# HD68_BNC_Breakout.net
KiCad netlist of a schematic drawn in Altium Designer
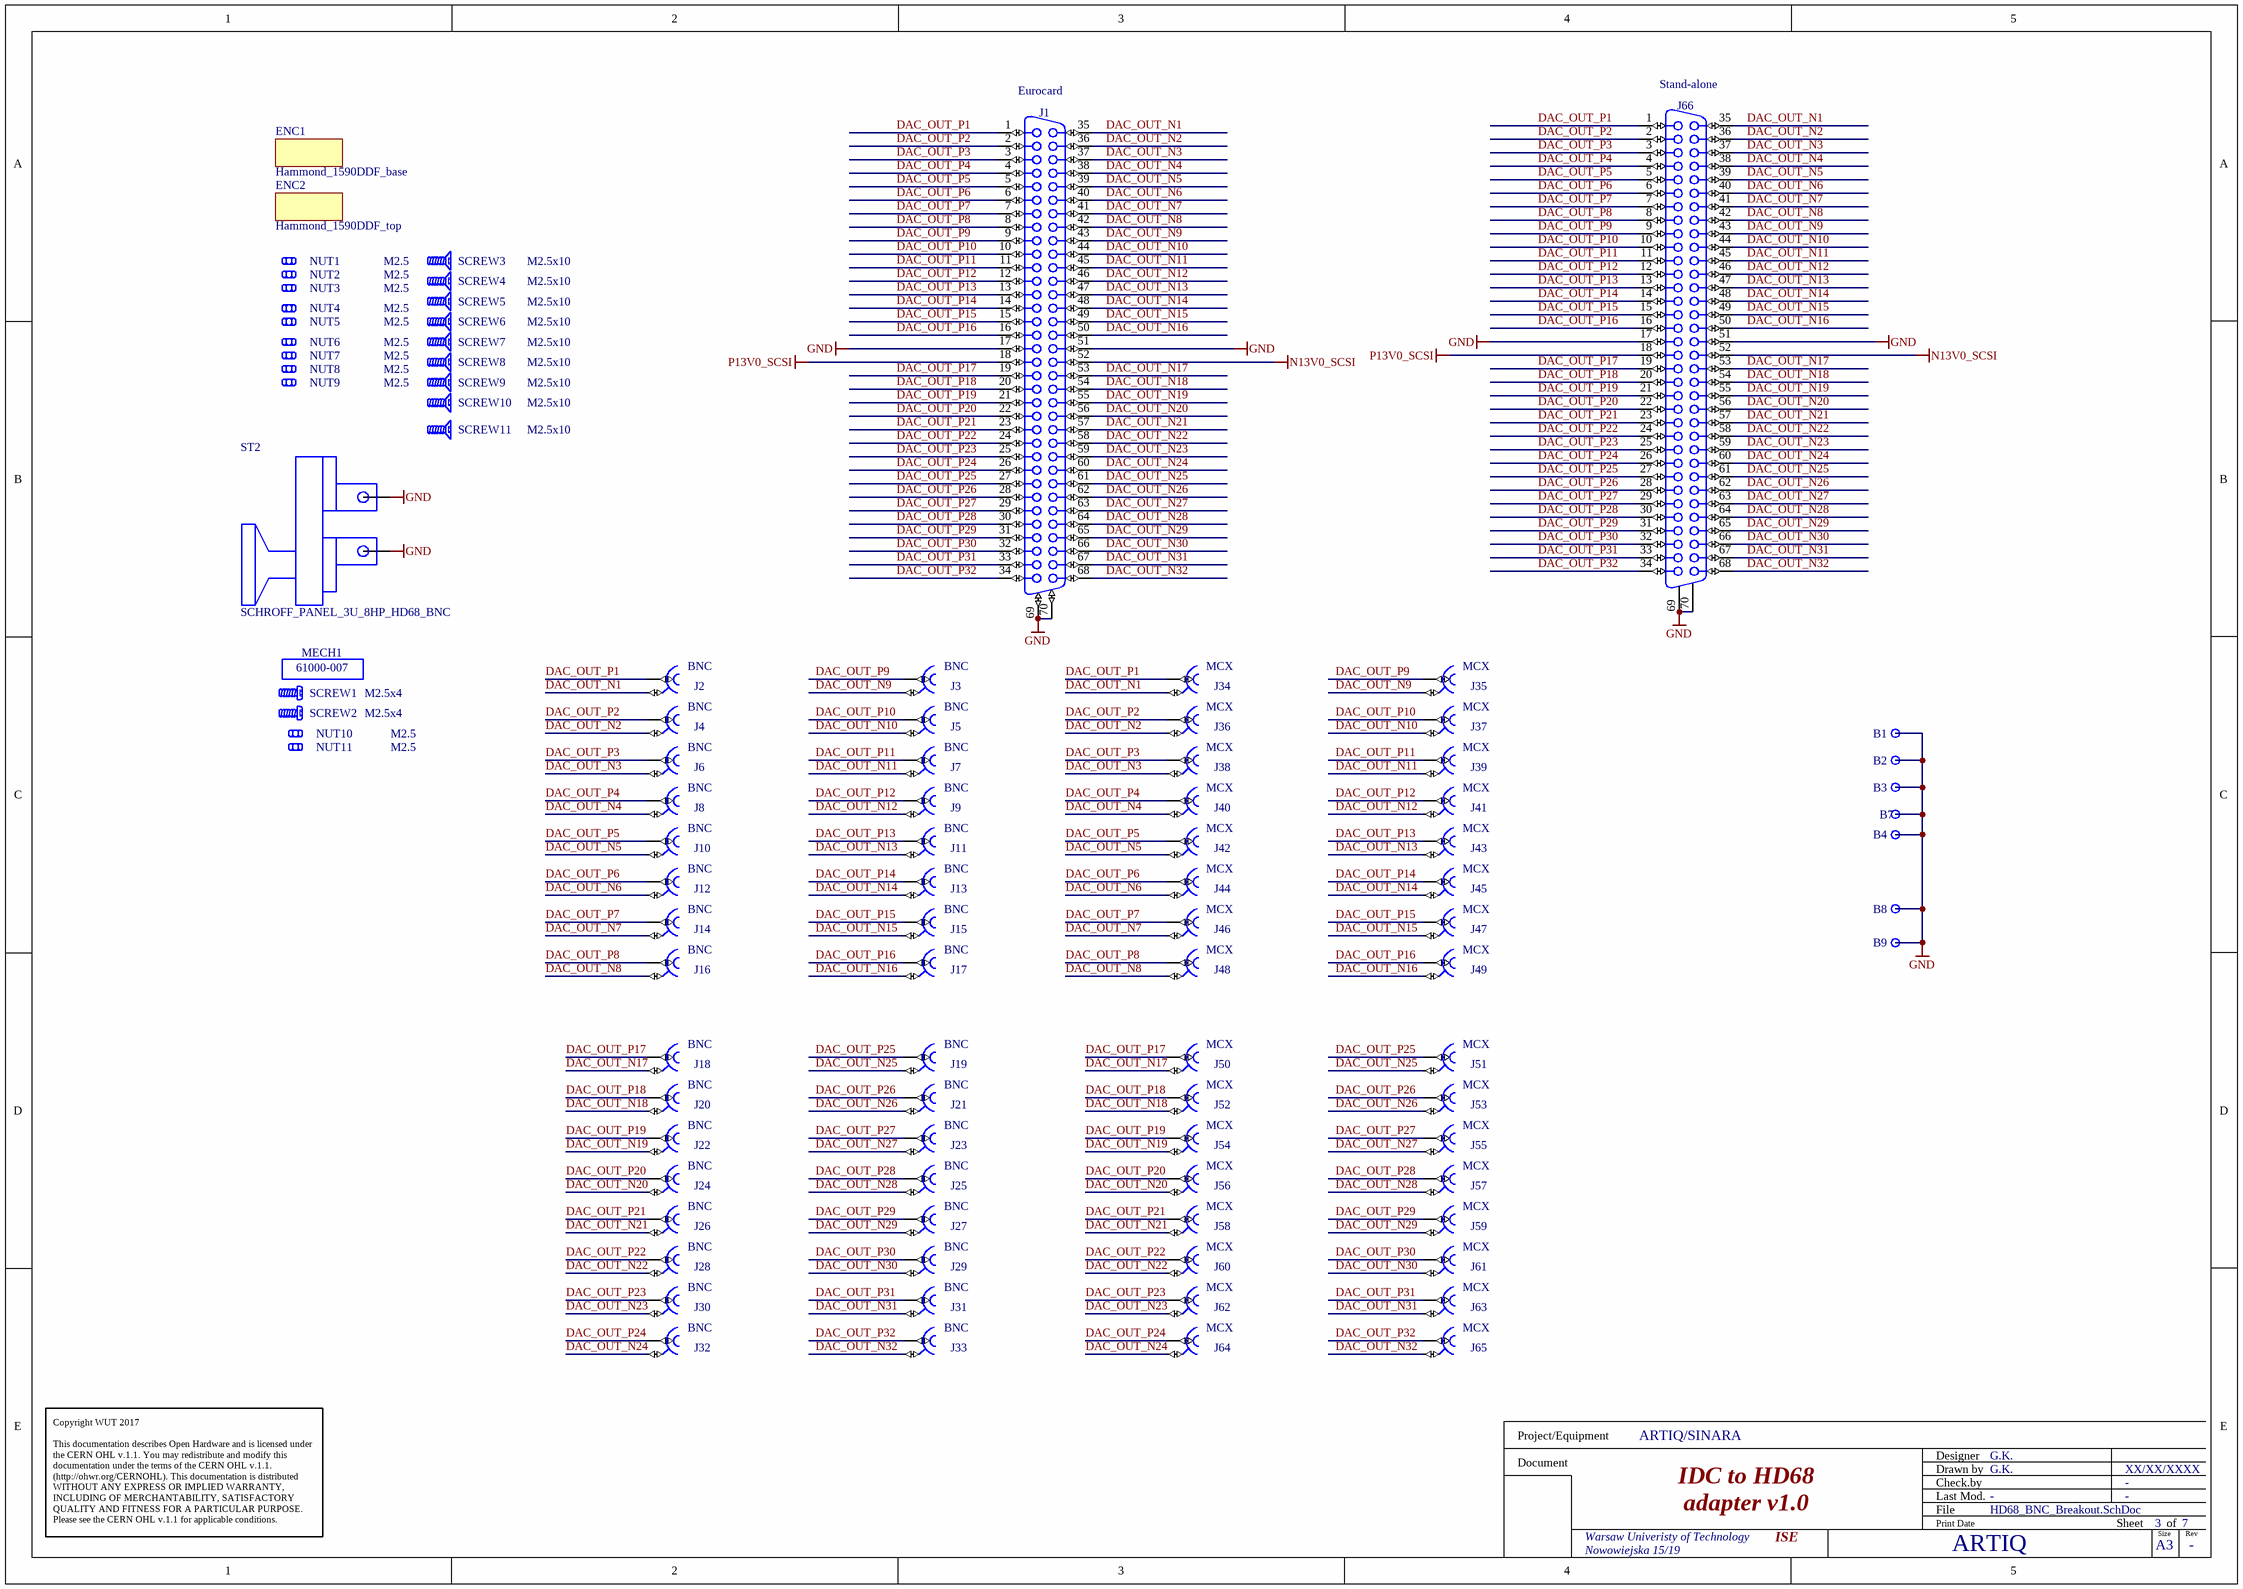
[diagram p0: HD68_BNC_Breakout.SchDoc]

(export (version "E")
  (design (tool "Eeschema 10.0.6"))
  (components
    (comp (ref "B1")
      (value "Plated Hole")
      (footprint "MTG270_500")
      (description "Single Terminal Socket")
      (fields (field (name "PART NUMBER") "PLATED_HOLE2.7_PAD5.0") (field (name "AUTHOR") "CERN DEM JMW"))
      (libsource (lib "Eletro-mechanical") (part "Single Terminal Socket"))
    )
    (comp (ref "B2")
      (value "Plated Hole")
      (footprint "MTG270_500")
      (description "Single Terminal Socket")
      (fields (field (name "PART NUMBER") "PLATED_HOLE2.7_PAD5.0") (field (name "AUTHOR") "CERN DEM JMW"))
      (libsource (lib "Eletro-mechanical") (part "Single Terminal Socket"))
    )
    (comp (ref "B3")
      (value "Plated Hole")
      (footprint "MTG270_500")
      (description "Single Terminal Socket")
      (fields (field (name "PART NUMBER") "PLATED_HOLE2.7_PAD5.0") (field (name "AUTHOR") "CERN DEM JMW"))
      (libsource (lib "Eletro-mechanical") (part "Single Terminal Socket"))
    )
    (comp (ref "B4")
      (value "Plated Hole")
      (footprint "MTG270_500")
      (description "Single Terminal Socket")
      (fields (field (name "PART NUMBER") "PLATED_HOLE2.7_PAD5.0") (field (name "AUTHOR") "CERN DEM JMW"))
      (libsource (lib "Eletro-mechanical") (part "Single Terminal Socket"))
    )
    (comp (ref "B7")
      (value "Plated Hole")
      (footprint "MTG270_500")
      (description "Single Terminal Socket")
      (fields (field (name "PART NUMBER") "PLATED_HOLE2.7_PAD5.0") (field (name "AUTHOR") "CERN DEM JMW"))
      (libsource (lib "Eletro-mechanical") (part "Single Terminal Socket"))
    )
    (comp (ref "B8")
      (value "Plated Hole")
      (footprint "MTG270_500")
      (description "Single Terminal Socket")
      (fields (field (name "PART NUMBER") "PLATED_HOLE2.7_PAD5.0") (field (name "AUTHOR") "CERN DEM JMW"))
      (libsource (lib "Eletro-mechanical") (part "Single Terminal Socket"))
    )
    (comp (ref "B9")
      (value "Plated Hole")
      (footprint "MTG270_500")
      (description "Single Terminal Socket")
      (fields (field (name "PART NUMBER") "PLATED_HOLE2.7_PAD5.0") (field (name "AUTHOR") "CERN DEM JMW"))
      (libsource (lib "Eletro-mechanical") (part "Single Terminal Socket"))
    )
    (comp (ref "ENC1")
      (value "Hammond_1590DDF_base")
      (footprint "1590DDF_base")
      (description "Hammond 1590DDF enclosure base part")
      (libsource (lib "Mechanical") (part "Hammond_1590DDF_base"))
    )
    (comp (ref "ENC2")
      (value "Hammond_1590DDF_top")
      (footprint "1590D-DD-E_LID_custom")
      (description "Hammond 1590DDF enclosure lid with custom cutouts")
      (libsource (lib "Mechanical") (part "Hammond_1590DDF_top_custom"))
    )
    (comp (ref "J1")
      (value "D-SUB")
      (footprint "TYCO_5787082-7")
      (description "68 contacts, AMPLIMITE .050\", Right Angled Receptacle Series III")
      (fields
        (field (name "PART NUMBER") "TYCO_5787082-7")
        (field (name "MANUFACTURER") "TYCO ELECTRONICS")
        (field (name "AUTHOR") "CERN DEM JLC")
      )
      (libsource (lib "Connectors") (part "TYCO_5787082-7"))
    )
    (comp (ref "J2")
      (value "BNC")
      (footprint "TYCO_5-1634506-1")
      (fields
        (field (name "PART NUMBER") "TYCO_5-1634506-1")
        (field (name "MANUFACTURER") "TYCO ELECTRONICS")
        (field (name "MANUFACTURER PART NUMBER") "5-1634506-1")
        (field (name "AUTHOR") "CERN DEM JLC")
      )
      (libsource (lib "Connectors") (part "Coax_1Female_1Shield"))
    )
    (comp (ref "J3")
      (value "BNC")
      (footprint "TYCO_5-1634506-1")
      (fields
        (field (name "PART NUMBER") "TYCO_5-1634506-1")
        (field (name "MANUFACTURER") "TYCO ELECTRONICS")
        (field (name "MANUFACTURER PART NUMBER") "5-1634506-1")
        (field (name "AUTHOR") "CERN DEM JLC")
      )
      (libsource (lib "Connectors") (part "Coax_1Female_1Shield"))
    )
    (comp (ref "J4")
      (value "BNC")
      (footprint "TYCO_5-1634506-1")
      (fields
        (field (name "PART NUMBER") "TYCO_5-1634506-1")
        (field (name "MANUFACTURER") "TYCO ELECTRONICS")
        (field (name "MANUFACTURER PART NUMBER") "5-1634506-1")
        (field (name "AUTHOR") "CERN DEM JLC")
      )
      (libsource (lib "Connectors") (part "Coax_1Female_1Shield"))
    )
    (comp (ref "J5")
      (value "BNC")
      (footprint "TYCO_5-1634506-1")
      (fields
        (field (name "PART NUMBER") "TYCO_5-1634506-1")
        (field (name "MANUFACTURER") "TYCO ELECTRONICS")
        (field (name "MANUFACTURER PART NUMBER") "5-1634506-1")
        (field (name "AUTHOR") "CERN DEM JLC")
      )
      (libsource (lib "Connectors") (part "Coax_1Female_1Shield"))
    )
    (comp (ref "J6")
      (value "BNC")
      (footprint "TYCO_5-1634506-1")
      (fields
        (field (name "PART NUMBER") "TYCO_5-1634506-1")
        (field (name "MANUFACTURER") "TYCO ELECTRONICS")
        (field (name "MANUFACTURER PART NUMBER") "5-1634506-1")
        (field (name "AUTHOR") "CERN DEM JLC")
      )
      (libsource (lib "Connectors") (part "Coax_1Female_1Shield"))
    )
    (comp (ref "J7")
      (value "BNC")
      (footprint "TYCO_5-1634506-1")
      (fields
        (field (name "PART NUMBER") "TYCO_5-1634506-1")
        (field (name "MANUFACTURER") "TYCO ELECTRONICS")
        (field (name "MANUFACTURER PART NUMBER") "5-1634506-1")
        (field (name "AUTHOR") "CERN DEM JLC")
      )
      (libsource (lib "Connectors") (part "Coax_1Female_1Shield"))
    )
    (comp (ref "J8")
      (value "BNC")
      (footprint "TYCO_5-1634506-1")
      (fields
        (field (name "PART NUMBER") "TYCO_5-1634506-1")
        (field (name "MANUFACTURER") "TYCO ELECTRONICS")
        (field (name "MANUFACTURER PART NUMBER") "5-1634506-1")
        (field (name "AUTHOR") "CERN DEM JLC")
      )
      (libsource (lib "Connectors") (part "Coax_1Female_1Shield"))
    )
    (comp (ref "J9")
      (value "BNC")
      (footprint "TYCO_5-1634506-1")
      (fields
        (field (name "PART NUMBER") "TYCO_5-1634506-1")
        (field (name "MANUFACTURER") "TYCO ELECTRONICS")
        (field (name "MANUFACTURER PART NUMBER") "5-1634506-1")
        (field (name "AUTHOR") "CERN DEM JLC")
      )
      (libsource (lib "Connectors") (part "Coax_1Female_1Shield"))
    )
    (comp (ref "J10")
      (value "BNC")
      (footprint "TYCO_5-1634506-1")
      (fields
        (field (name "PART NUMBER") "TYCO_5-1634506-1")
        (field (name "MANUFACTURER") "TYCO ELECTRONICS")
        (field (name "MANUFACTURER PART NUMBER") "5-1634506-1")
        (field (name "AUTHOR") "CERN DEM JLC")
      )
      (libsource (lib "Connectors") (part "Coax_1Female_1Shield"))
    )
    (comp (ref "J11")
      (value "BNC")
      (footprint "TYCO_5-1634506-1")
      (fields
        (field (name "PART NUMBER") "TYCO_5-1634506-1")
        (field (name "MANUFACTURER") "TYCO ELECTRONICS")
        (field (name "MANUFACTURER PART NUMBER") "5-1634506-1")
        (field (name "AUTHOR") "CERN DEM JLC")
      )
      (libsource (lib "Connectors") (part "Coax_1Female_1Shield"))
    )
    (comp (ref "J12")
      (value "BNC")
      (footprint "TYCO_5-1634506-1")
      (fields
        (field (name "PART NUMBER") "TYCO_5-1634506-1")
        (field (name "MANUFACTURER") "TYCO ELECTRONICS")
        (field (name "MANUFACTURER PART NUMBER") "5-1634506-1")
        (field (name "AUTHOR") "CERN DEM JLC")
      )
      (libsource (lib "Connectors") (part "Coax_1Female_1Shield"))
    )
    (comp (ref "J13")
      (value "BNC")
      (footprint "TYCO_5-1634506-1")
      (fields
        (field (name "PART NUMBER") "TYCO_5-1634506-1")
        (field (name "MANUFACTURER") "TYCO ELECTRONICS")
        (field (name "MANUFACTURER PART NUMBER") "5-1634506-1")
        (field (name "AUTHOR") "CERN DEM JLC")
      )
      (libsource (lib "Connectors") (part "Coax_1Female_1Shield"))
    )
    (comp (ref "J14")
      (value "BNC")
      (footprint "TYCO_5-1634506-1")
      (fields
        (field (name "PART NUMBER") "TYCO_5-1634506-1")
        (field (name "MANUFACTURER") "TYCO ELECTRONICS")
        (field (name "MANUFACTURER PART NUMBER") "5-1634506-1")
        (field (name "AUTHOR") "CERN DEM JLC")
      )
      (libsource (lib "Connectors") (part "Coax_1Female_1Shield"))
    )
    (comp (ref "J15")
      (value "BNC")
      (footprint "TYCO_5-1634506-1")
      (fields
        (field (name "PART NUMBER") "TYCO_5-1634506-1")
        (field (name "MANUFACTURER") "TYCO ELECTRONICS")
        (field (name "MANUFACTURER PART NUMBER") "5-1634506-1")
        (field (name "AUTHOR") "CERN DEM JLC")
      )
      (libsource (lib "Connectors") (part "Coax_1Female_1Shield"))
    )
    (comp (ref "J16")
      (value "BNC")
      (footprint "TYCO_5-1634506-1")
      (fields
        (field (name "PART NUMBER") "TYCO_5-1634506-1")
        (field (name "MANUFACTURER") "TYCO ELECTRONICS")
        (field (name "MANUFACTURER PART NUMBER") "5-1634506-1")
        (field (name "AUTHOR") "CERN DEM JLC")
      )
      (libsource (lib "Connectors") (part "Coax_1Female_1Shield"))
    )
    (comp (ref "J17")
      (value "BNC")
      (footprint "TYCO_5-1634506-1")
      (fields
        (field (name "PART NUMBER") "TYCO_5-1634506-1")
        (field (name "MANUFACTURER") "TYCO ELECTRONICS")
        (field (name "MANUFACTURER PART NUMBER") "5-1634506-1")
        (field (name "AUTHOR") "CERN DEM JLC")
      )
      (libsource (lib "Connectors") (part "Coax_1Female_1Shield"))
    )
    (comp (ref "J18")
      (value "BNC")
      (footprint "TYCO_5-1634506-1")
      (fields
        (field (name "PART NUMBER") "TYCO_5-1634506-1")
        (field (name "MANUFACTURER") "TYCO ELECTRONICS")
        (field (name "MANUFACTURER PART NUMBER") "5-1634506-1")
        (field (name "AUTHOR") "CERN DEM JLC")
      )
      (libsource (lib "Connectors") (part "Coax_1Female_1Shield"))
    )
    (comp (ref "J19")
      (value "BNC")
      (footprint "TYCO_5-1634506-1")
      (fields
        (field (name "PART NUMBER") "TYCO_5-1634506-1")
        (field (name "MANUFACTURER") "TYCO ELECTRONICS")
        (field (name "MANUFACTURER PART NUMBER") "5-1634506-1")
        (field (name "AUTHOR") "CERN DEM JLC")
      )
      (libsource (lib "Connectors") (part "Coax_1Female_1Shield"))
    )
    (comp (ref "J20")
      (value "BNC")
      (footprint "TYCO_5-1634506-1")
      (fields
        (field (name "PART NUMBER") "TYCO_5-1634506-1")
        (field (name "MANUFACTURER") "TYCO ELECTRONICS")
        (field (name "MANUFACTURER PART NUMBER") "5-1634506-1")
        (field (name "AUTHOR") "CERN DEM JLC")
      )
      (libsource (lib "Connectors") (part "Coax_1Female_1Shield"))
    )
    (comp (ref "J21")
      (value "BNC")
      (footprint "TYCO_5-1634506-1")
      (fields
        (field (name "PART NUMBER") "TYCO_5-1634506-1")
        (field (name "MANUFACTURER") "TYCO ELECTRONICS")
        (field (name "MANUFACTURER PART NUMBER") "5-1634506-1")
        (field (name "AUTHOR") "CERN DEM JLC")
      )
      (libsource (lib "Connectors") (part "Coax_1Female_1Shield"))
    )
    (comp (ref "J22")
      (value "BNC")
      (footprint "TYCO_5-1634506-1")
      (fields
        (field (name "PART NUMBER") "TYCO_5-1634506-1")
        (field (name "MANUFACTURER") "TYCO ELECTRONICS")
        (field (name "MANUFACTURER PART NUMBER") "5-1634506-1")
        (field (name "AUTHOR") "CERN DEM JLC")
      )
      (libsource (lib "Connectors") (part "Coax_1Female_1Shield"))
    )
    (comp (ref "J23")
      (value "BNC")
      (footprint "TYCO_5-1634506-1")
      (fields
        (field (name "PART NUMBER") "TYCO_5-1634506-1")
        (field (name "MANUFACTURER") "TYCO ELECTRONICS")
        (field (name "MANUFACTURER PART NUMBER") "5-1634506-1")
        (field (name "AUTHOR") "CERN DEM JLC")
      )
      (libsource (lib "Connectors") (part "Coax_1Female_1Shield"))
    )
    (comp (ref "J24")
      (value "BNC")
      (footprint "TYCO_5-1634506-1")
      (fields
        (field (name "PART NUMBER") "TYCO_5-1634506-1")
        (field (name "MANUFACTURER") "TYCO ELECTRONICS")
        (field (name "MANUFACTURER PART NUMBER") "5-1634506-1")
        (field (name "AUTHOR") "CERN DEM JLC")
      )
      (libsource (lib "Connectors") (part "Coax_1Female_1Shield"))
    )
    (comp (ref "J25")
      (value "BNC")
      (footprint "TYCO_5-1634506-1")
      (fields
        (field (name "PART NUMBER") "TYCO_5-1634506-1")
        (field (name "MANUFACTURER") "TYCO ELECTRONICS")
        (field (name "MANUFACTURER PART NUMBER") "5-1634506-1")
        (field (name "AUTHOR") "CERN DEM JLC")
      )
      (libsource (lib "Connectors") (part "Coax_1Female_1Shield"))
    )
    (comp (ref "J26")
      (value "BNC")
      (footprint "TYCO_5-1634506-1")
      (fields
        (field (name "PART NUMBER") "TYCO_5-1634506-1")
        (field (name "MANUFACTURER") "TYCO ELECTRONICS")
        (field (name "MANUFACTURER PART NUMBER") "5-1634506-1")
        (field (name "AUTHOR") "CERN DEM JLC")
      )
      (libsource (lib "Connectors") (part "Coax_1Female_1Shield"))
    )
    (comp (ref "J27")
      (value "BNC")
      (footprint "TYCO_5-1634506-1")
      (fields
        (field (name "PART NUMBER") "TYCO_5-1634506-1")
        (field (name "MANUFACTURER") "TYCO ELECTRONICS")
        (field (name "MANUFACTURER PART NUMBER") "5-1634506-1")
        (field (name "AUTHOR") "CERN DEM JLC")
      )
      (libsource (lib "Connectors") (part "Coax_1Female_1Shield"))
    )
    (comp (ref "J28")
      (value "BNC")
      (footprint "TYCO_5-1634506-1")
      (fields
        (field (name "PART NUMBER") "TYCO_5-1634506-1")
        (field (name "MANUFACTURER") "TYCO ELECTRONICS")
        (field (name "MANUFACTURER PART NUMBER") "5-1634506-1")
        (field (name "AUTHOR") "CERN DEM JLC")
      )
      (libsource (lib "Connectors") (part "Coax_1Female_1Shield"))
    )
    (comp (ref "J29")
      (value "BNC")
      (footprint "TYCO_5-1634506-1")
      (fields
        (field (name "PART NUMBER") "TYCO_5-1634506-1")
        (field (name "MANUFACTURER") "TYCO ELECTRONICS")
        (field (name "MANUFACTURER PART NUMBER") "5-1634506-1")
        (field (name "AUTHOR") "CERN DEM JLC")
      )
      (libsource (lib "Connectors") (part "Coax_1Female_1Shield"))
    )
    (comp (ref "J30")
      (value "BNC")
      (footprint "TYCO_5-1634506-1")
      (fields
        (field (name "PART NUMBER") "TYCO_5-1634506-1")
        (field (name "MANUFACTURER") "TYCO ELECTRONICS")
        (field (name "MANUFACTURER PART NUMBER") "5-1634506-1")
        (field (name "AUTHOR") "CERN DEM JLC")
      )
      (libsource (lib "Connectors") (part "Coax_1Female_1Shield"))
    )
    (comp (ref "J31")
      (value "BNC")
      (footprint "TYCO_5-1634506-1")
      (fields
        (field (name "PART NUMBER") "TYCO_5-1634506-1")
        (field (name "MANUFACTURER") "TYCO ELECTRONICS")
        (field (name "MANUFACTURER PART NUMBER") "5-1634506-1")
        (field (name "AUTHOR") "CERN DEM JLC")
      )
      (libsource (lib "Connectors") (part "Coax_1Female_1Shield"))
    )
    (comp (ref "J32")
      (value "BNC")
      (footprint "TYCO_5-1634506-1")
      (fields
        (field (name "PART NUMBER") "TYCO_5-1634506-1")
        (field (name "MANUFACTURER") "TYCO ELECTRONICS")
        (field (name "MANUFACTURER PART NUMBER") "5-1634506-1")
        (field (name "AUTHOR") "CERN DEM JLC")
      )
      (libsource (lib "Connectors") (part "Coax_1Female_1Shield"))
    )
    (comp (ref "J33")
      (value "BNC")
      (footprint "TYCO_5-1634506-1")
      (fields
        (field (name "PART NUMBER") "TYCO_5-1634506-1")
        (field (name "MANUFACTURER") "TYCO ELECTRONICS")
        (field (name "MANUFACTURER PART NUMBER") "5-1634506-1")
        (field (name "AUTHOR") "CERN DEM JLC")
      )
      (libsource (lib "Connectors") (part "Coax_1Female_1Shield"))
    )
    (comp (ref "J34")
      (value "MCX")
      (footprint "AMPHENOL_919-109J-51PX")
      (fields
        (field (name "PART NUMBER") "AMPHENOL_919-109J-51PX")
        (field (name "MANUFACTURER") "AMPHENOL")
        (field (name "MANUFACTURER PART NUMBER") "919-109J-51PX (MCX6251B1-3GT30G-50)")
        (field (name "AUTHOR") "CERN DEM BC")
      )
      (libsource (lib "Connectors") (part "Coax_1Female_1Shield"))
    )
    (comp (ref "J35")
      (value "MCX")
      (footprint "AMPHENOL_919-109J-51PX")
      (fields
        (field (name "PART NUMBER") "AMPHENOL_919-109J-51PX")
        (field (name "MANUFACTURER") "AMPHENOL")
        (field (name "MANUFACTURER PART NUMBER") "919-109J-51PX (MCX6251B1-3GT30G-50)")
        (field (name "AUTHOR") "CERN DEM BC")
      )
      (libsource (lib "Connectors") (part "Coax_1Female_1Shield"))
    )
    (comp (ref "J36")
      (value "MCX")
      (footprint "AMPHENOL_919-109J-51PX")
      (fields
        (field (name "PART NUMBER") "AMPHENOL_919-109J-51PX")
        (field (name "MANUFACTURER") "AMPHENOL")
        (field (name "MANUFACTURER PART NUMBER") "919-109J-51PX (MCX6251B1-3GT30G-50)")
        (field (name "AUTHOR") "CERN DEM BC")
      )
      (libsource (lib "Connectors") (part "Coax_1Female_1Shield"))
    )
    (comp (ref "J37")
      (value "MCX")
      (footprint "AMPHENOL_919-109J-51PX")
      (fields
        (field (name "PART NUMBER") "AMPHENOL_919-109J-51PX")
        (field (name "MANUFACTURER") "AMPHENOL")
        (field (name "MANUFACTURER PART NUMBER") "919-109J-51PX (MCX6251B1-3GT30G-50)")
        (field (name "AUTHOR") "CERN DEM BC")
      )
      (libsource (lib "Connectors") (part "Coax_1Female_1Shield"))
    )
    (comp (ref "J38")
      (value "MCX")
      (footprint "AMPHENOL_919-109J-51PX")
      (fields
        (field (name "PART NUMBER") "AMPHENOL_919-109J-51PX")
        (field (name "MANUFACTURER") "AMPHENOL")
        (field (name "MANUFACTURER PART NUMBER") "919-109J-51PX (MCX6251B1-3GT30G-50)")
        (field (name "AUTHOR") "CERN DEM BC")
      )
      (libsource (lib "Connectors") (part "Coax_1Female_1Shield"))
    )
    (comp (ref "J39")
      (value "MCX")
      (footprint "AMPHENOL_919-109J-51PX")
      (fields
        (field (name "PART NUMBER") "AMPHENOL_919-109J-51PX")
        (field (name "MANUFACTURER") "AMPHENOL")
        (field (name "MANUFACTURER PART NUMBER") "919-109J-51PX (MCX6251B1-3GT30G-50)")
        (field (name "AUTHOR") "CERN DEM BC")
      )
      (libsource (lib "Connectors") (part "Coax_1Female_1Shield"))
    )
    (comp (ref "J40")
      (value "MCX")
      (footprint "AMPHENOL_919-109J-51PX")
      (fields
        (field (name "PART NUMBER") "AMPHENOL_919-109J-51PX")
        (field (name "MANUFACTURER") "AMPHENOL")
        (field (name "MANUFACTURER PART NUMBER") "919-109J-51PX (MCX6251B1-3GT30G-50)")
        (field (name "AUTHOR") "CERN DEM BC")
      )
      (libsource (lib "Connectors") (part "Coax_1Female_1Shield"))
    )
    (comp (ref "J41")
      (value "MCX")
      (footprint "AMPHENOL_919-109J-51PX")
      (fields
        (field (name "PART NUMBER") "AMPHENOL_919-109J-51PX")
        (field (name "MANUFACTURER") "AMPHENOL")
        (field (name "MANUFACTURER PART NUMBER") "919-109J-51PX (MCX6251B1-3GT30G-50)")
        (field (name "AUTHOR") "CERN DEM BC")
      )
      (libsource (lib "Connectors") (part "Coax_1Female_1Shield"))
    )
    (comp (ref "J42")
      (value "MCX")
      (footprint "AMPHENOL_919-109J-51PX")
      (fields
        (field (name "PART NUMBER") "AMPHENOL_919-109J-51PX")
        (field (name "MANUFACTURER") "AMPHENOL")
        (field (name "MANUFACTURER PART NUMBER") "919-109J-51PX (MCX6251B1-3GT30G-50)")
        (field (name "AUTHOR") "CERN DEM BC")
      )
      (libsource (lib "Connectors") (part "Coax_1Female_1Shield"))
    )
    (comp (ref "J43")
      (value "MCX")
      (footprint "AMPHENOL_919-109J-51PX")
      (fields
        (field (name "PART NUMBER") "AMPHENOL_919-109J-51PX")
        (field (name "MANUFACTURER") "AMPHENOL")
        (field (name "MANUFACTURER PART NUMBER") "919-109J-51PX (MCX6251B1-3GT30G-50)")
        (field (name "AUTHOR") "CERN DEM BC")
      )
      (libsource (lib "Connectors") (part "Coax_1Female_1Shield"))
    )
    (comp (ref "J44")
      (value "MCX")
      (footprint "AMPHENOL_919-109J-51PX")
      (fields
        (field (name "PART NUMBER") "AMPHENOL_919-109J-51PX")
        (field (name "MANUFACTURER") "AMPHENOL")
        (field (name "MANUFACTURER PART NUMBER") "919-109J-51PX (MCX6251B1-3GT30G-50)")
        (field (name "AUTHOR") "CERN DEM BC")
      )
      (libsource (lib "Connectors") (part "Coax_1Female_1Shield"))
    )
    (comp (ref "J45")
      (value "MCX")
      (footprint "AMPHENOL_919-109J-51PX")
      (fields
        (field (name "PART NUMBER") "AMPHENOL_919-109J-51PX")
        (field (name "MANUFACTURER") "AMPHENOL")
        (field (name "MANUFACTURER PART NUMBER") "919-109J-51PX (MCX6251B1-3GT30G-50)")
        (field (name "AUTHOR") "CERN DEM BC")
      )
      (libsource (lib "Connectors") (part "Coax_1Female_1Shield"))
    )
    (comp (ref "J46")
      (value "MCX")
      (footprint "AMPHENOL_919-109J-51PX")
      (fields
        (field (name "PART NUMBER") "AMPHENOL_919-109J-51PX")
        (field (name "MANUFACTURER") "AMPHENOL")
        (field (name "MANUFACTURER PART NUMBER") "919-109J-51PX (MCX6251B1-3GT30G-50)")
        (field (name "AUTHOR") "CERN DEM BC")
      )
      (libsource (lib "Connectors") (part "Coax_1Female_1Shield"))
    )
    (comp (ref "J47")
      (value "MCX")
      (footprint "AMPHENOL_919-109J-51PX")
      (fields
        (field (name "PART NUMBER") "AMPHENOL_919-109J-51PX")
        (field (name "MANUFACTURER") "AMPHENOL")
        (field (name "MANUFACTURER PART NUMBER") "919-109J-51PX (MCX6251B1-3GT30G-50)")
        (field (name "AUTHOR") "CERN DEM BC")
      )
      (libsource (lib "Connectors") (part "Coax_1Female_1Shield"))
    )
    (comp (ref "J48")
      (value "MCX")
      (footprint "AMPHENOL_919-109J-51PX")
      (fields
        (field (name "PART NUMBER") "AMPHENOL_919-109J-51PX")
        (field (name "MANUFACTURER") "AMPHENOL")
        (field (name "MANUFACTURER PART NUMBER") "919-109J-51PX (MCX6251B1-3GT30G-50)")
        (field (name "AUTHOR") "CERN DEM BC")
      )
      (libsource (lib "Connectors") (part "Coax_1Female_1Shield"))
    )
    (comp (ref "J49")
      (value "MCX")
      (footprint "AMPHENOL_919-109J-51PX")
      (fields
        (field (name "PART NUMBER") "AMPHENOL_919-109J-51PX")
        (field (name "MANUFACTURER") "AMPHENOL")
        (field (name "MANUFACTURER PART NUMBER") "919-109J-51PX (MCX6251B1-3GT30G-50)")
        (field (name "AUTHOR") "CERN DEM BC")
      )
      (libsource (lib "Connectors") (part "Coax_1Female_1Shield"))
    )
    (comp (ref "J50")
      (value "MCX")
      (footprint "AMPHENOL_919-109J-51PX")
      (fields
        (field (name "PART NUMBER") "AMPHENOL_919-109J-51PX")
        (field (name "MANUFACTURER") "AMPHENOL")
        (field (name "MANUFACTURER PART NUMBER") "919-109J-51PX (MCX6251B1-3GT30G-50)")
        (field (name "AUTHOR") "CERN DEM BC")
      )
      (libsource (lib "Connectors") (part "Coax_1Female_1Shield"))
    )
    (comp (ref "J51")
      (value "MCX")
      (footprint "AMPHENOL_919-109J-51PX")
      (fields
        (field (name "PART NUMBER") "AMPHENOL_919-109J-51PX")
        (field (name "MANUFACTURER") "AMPHENOL")
        (field (name "MANUFACTURER PART NUMBER") "919-109J-51PX (MCX6251B1-3GT30G-50)")
        (field (name "AUTHOR") "CERN DEM BC")
      )
      (libsource (lib "Connectors") (part "Coax_1Female_1Shield"))
    )
    (comp (ref "J52")
      (value "MCX")
      (footprint "AMPHENOL_919-109J-51PX")
      (fields
        (field (name "PART NUMBER") "AMPHENOL_919-109J-51PX")
        (field (name "MANUFACTURER") "AMPHENOL")
        (field (name "MANUFACTURER PART NUMBER") "919-109J-51PX (MCX6251B1-3GT30G-50)")
        (field (name "AUTHOR") "CERN DEM BC")
      )
      (libsource (lib "Connectors") (part "Coax_1Female_1Shield"))
    )
    (comp (ref "J53")
      (value "MCX")
      (footprint "AMPHENOL_919-109J-51PX")
      (fields
        (field (name "PART NUMBER") "AMPHENOL_919-109J-51PX")
        (field (name "MANUFACTURER") "AMPHENOL")
        (field (name "MANUFACTURER PART NUMBER") "919-109J-51PX (MCX6251B1-3GT30G-50)")
        (field (name "AUTHOR") "CERN DEM BC")
      )
      (libsource (lib "Connectors") (part "Coax_1Female_1Shield"))
    )
    (comp (ref "J54")
      (value "MCX")
      (footprint "AMPHENOL_919-109J-51PX")
      (fields
        (field (name "PART NUMBER") "AMPHENOL_919-109J-51PX")
        (field (name "MANUFACTURER") "AMPHENOL")
        (field (name "MANUFACTURER PART NUMBER") "919-109J-51PX (MCX6251B1-3GT30G-50)")
        (field (name "AUTHOR") "CERN DEM BC")
      )
      (libsource (lib "Connectors") (part "Coax_1Female_1Shield"))
    )
    (comp (ref "J55")
      (value "MCX")
      (footprint "AMPHENOL_919-109J-51PX")
      (fields
        (field (name "PART NUMBER") "AMPHENOL_919-109J-51PX")
        (field (name "MANUFACTURER") "AMPHENOL")
        (field (name "MANUFACTURER PART NUMBER") "919-109J-51PX (MCX6251B1-3GT30G-50)")
        (field (name "AUTHOR") "CERN DEM BC")
      )
      (libsource (lib "Connectors") (part "Coax_1Female_1Shield"))
    )
    (comp (ref "J56")
      (value "MCX")
      (footprint "AMPHENOL_919-109J-51PX")
      (fields
        (field (name "PART NUMBER") "AMPHENOL_919-109J-51PX")
        (field (name "MANUFACTURER") "AMPHENOL")
        (field (name "MANUFACTURER PART NUMBER") "919-109J-51PX (MCX6251B1-3GT30G-50)")
        (field (name "AUTHOR") "CERN DEM BC")
      )
      (libsource (lib "Connectors") (part "Coax_1Female_1Shield"))
    )
    (comp (ref "J57")
      (value "MCX")
      (footprint "AMPHENOL_919-109J-51PX")
      (fields
        (field (name "PART NUMBER") "AMPHENOL_919-109J-51PX")
        (field (name "MANUFACTURER") "AMPHENOL")
        (field (name "MANUFACTURER PART NUMBER") "919-109J-51PX (MCX6251B1-3GT30G-50)")
        (field (name "AUTHOR") "CERN DEM BC")
      )
      (libsource (lib "Connectors") (part "Coax_1Female_1Shield"))
    )
    (comp (ref "J58")
      (value "MCX")
      (footprint "AMPHENOL_919-109J-51PX")
      (fields
        (field (name "PART NUMBER") "AMPHENOL_919-109J-51PX")
        (field (name "MANUFACTURER") "AMPHENOL")
        (field (name "MANUFACTURER PART NUMBER") "919-109J-51PX (MCX6251B1-3GT30G-50)")
        (field (name "AUTHOR") "CERN DEM BC")
      )
      (libsource (lib "Connectors") (part "Coax_1Female_1Shield"))
    )
    (comp (ref "J59")
      (value "MCX")
      (footprint "AMPHENOL_919-109J-51PX")
      (fields
        (field (name "PART NUMBER") "AMPHENOL_919-109J-51PX")
        (field (name "MANUFACTURER") "AMPHENOL")
        (field (name "MANUFACTURER PART NUMBER") "919-109J-51PX (MCX6251B1-3GT30G-50)")
        (field (name "AUTHOR") "CERN DEM BC")
      )
      (libsource (lib "Connectors") (part "Coax_1Female_1Shield"))
    )
    (comp (ref "J60")
      (value "MCX")
      (footprint "AMPHENOL_919-109J-51PX")
      (fields
        (field (name "PART NUMBER") "AMPHENOL_919-109J-51PX")
        (field (name "MANUFACTURER") "AMPHENOL")
        (field (name "MANUFACTURER PART NUMBER") "919-109J-51PX (MCX6251B1-3GT30G-50)")
        (field (name "AUTHOR") "CERN DEM BC")
      )
      (libsource (lib "Connectors") (part "Coax_1Female_1Shield"))
    )
    (comp (ref "J61")
      (value "MCX")
      (footprint "AMPHENOL_919-109J-51PX")
      (fields
        (field (name "PART NUMBER") "AMPHENOL_919-109J-51PX")
        (field (name "MANUFACTURER") "AMPHENOL")
        (field (name "MANUFACTURER PART NUMBER") "919-109J-51PX (MCX6251B1-3GT30G-50)")
        (field (name "AUTHOR") "CERN DEM BC")
      )
      (libsource (lib "Connectors") (part "Coax_1Female_1Shield"))
    )
    (comp (ref "J62")
      (value "MCX")
      (footprint "AMPHENOL_919-109J-51PX")
      (fields
        (field (name "PART NUMBER") "AMPHENOL_919-109J-51PX")
        (field (name "MANUFACTURER") "AMPHENOL")
        (field (name "MANUFACTURER PART NUMBER") "919-109J-51PX (MCX6251B1-3GT30G-50)")
        (field (name "AUTHOR") "CERN DEM BC")
      )
      (libsource (lib "Connectors") (part "Coax_1Female_1Shield"))
    )
    (comp (ref "J63")
      (value "MCX")
      (footprint "AMPHENOL_919-109J-51PX")
      (fields
        (field (name "PART NUMBER") "AMPHENOL_919-109J-51PX")
        (field (name "MANUFACTURER") "AMPHENOL")
        (field (name "MANUFACTURER PART NUMBER") "919-109J-51PX (MCX6251B1-3GT30G-50)")
        (field (name "AUTHOR") "CERN DEM BC")
      )
      (libsource (lib "Connectors") (part "Coax_1Female_1Shield"))
    )
    (comp (ref "J64")
      (value "MCX")
      (footprint "AMPHENOL_919-109J-51PX")
      (fields
        (field (name "PART NUMBER") "AMPHENOL_919-109J-51PX")
        (field (name "MANUFACTURER") "AMPHENOL")
        (field (name "MANUFACTURER PART NUMBER") "919-109J-51PX (MCX6251B1-3GT30G-50)")
        (field (name "AUTHOR") "CERN DEM BC")
      )
      (libsource (lib "Connectors") (part "Coax_1Female_1Shield"))
    )
    (comp (ref "J65")
      (value "MCX")
      (footprint "AMPHENOL_919-109J-51PX")
      (fields
        (field (name "PART NUMBER") "AMPHENOL_919-109J-51PX")
        (field (name "MANUFACTURER") "AMPHENOL")
        (field (name "MANUFACTURER PART NUMBER") "919-109J-51PX (MCX6251B1-3GT30G-50)")
        (field (name "AUTHOR") "CERN DEM BC")
      )
      (libsource (lib "Connectors") (part "Coax_1Female_1Shield"))
    )
    (comp (ref "J66")
      (value "AMPLIMITE")
      (footprint "TYCO_5749721-7")
      (description "AMPLIMITE .050 Series, 68 Positions Vertical Receptacle")
      (fields
        (field (name "PART NUMBER") "TYCO_5749721-7")
        (field (name "MANUFACTURER") "TYCO ELECTRONICS")
        (field (name "AUTHOR") "CERN DEM HF")
      )
      (libsource (lib "Connectors") (part "TYCO_5749721-7"))
    )
    (comp (ref "MECH1")
      (value "61000-007")
      (footprint "GENERIC_MECH")
      (description "PCB Solder Side Cover, 3 U, 100 mm x 160 mm, 55°C Schroff insulating plate")
      (fields (field (name "MANUFACTURER") "Schroff") (field (name "AUTHOR") "GK"))
      (libsource (lib "Mechanical") (part "Generic_mechanical"))
    )
    (comp (ref "NUT1")
      (value "M2.5")
      (footprint "BOSSARD_BN628-1241427_v")
      (description "Nut")
      (fields
        (field (name "PART NUMBER") "BOSSARD_BN628-1241427_v")
        (field (name "MANUFACTURER") "BOSSARD")
        (field (name "AUTHOR") "CERN DEM JMW")
      )
      (libsource (lib "Eletro-mechanical") (part "Nut"))
    )
    (comp (ref "NUT2")
      (value "M2.5")
      (footprint "BOSSARD_BN628-1241427_v")
      (description "Nut")
      (fields
        (field (name "PART NUMBER") "BOSSARD_BN628-1241427_v")
        (field (name "MANUFACTURER") "BOSSARD")
        (field (name "AUTHOR") "CERN DEM JMW")
      )
      (libsource (lib "Eletro-mechanical") (part "Nut"))
    )
    (comp (ref "NUT3")
      (value "M2.5")
      (footprint "BOSSARD_BN628-1241427_v")
      (description "Nut")
      (fields
        (field (name "PART NUMBER") "BOSSARD_BN628-1241427_v")
        (field (name "MANUFACTURER") "BOSSARD")
        (field (name "AUTHOR") "CERN DEM JMW")
      )
      (libsource (lib "Eletro-mechanical") (part "Nut"))
    )
    (comp (ref "NUT4")
      (value "M2.5")
      (footprint "BOSSARD_BN628-1241427_v")
      (description "Nut")
      (fields
        (field (name "PART NUMBER") "BOSSARD_BN628-1241427_v")
        (field (name "MANUFACTURER") "BOSSARD")
        (field (name "AUTHOR") "CERN DEM JMW")
      )
      (libsource (lib "Eletro-mechanical") (part "Nut"))
    )
    (comp (ref "NUT5")
      (value "M2.5")
      (footprint "BOSSARD_BN628-1241427_v")
      (description "Nut")
      (fields
        (field (name "PART NUMBER") "BOSSARD_BN628-1241427_v")
        (field (name "MANUFACTURER") "BOSSARD")
        (field (name "AUTHOR") "CERN DEM JMW")
      )
      (libsource (lib "Eletro-mechanical") (part "Nut"))
    )
    (comp (ref "NUT6")
      (value "M2.5")
      (footprint "BOSSARD_BN628-1241427_v")
      (description "Nut")
      (fields
        (field (name "PART NUMBER") "BOSSARD_BN628-1241427_v")
        (field (name "MANUFACTURER") "BOSSARD")
        (field (name "AUTHOR") "CERN DEM JMW")
      )
      (libsource (lib "Eletro-mechanical") (part "Nut"))
    )
    (comp (ref "NUT7")
      (value "M2.5")
      (footprint "BOSSARD_BN628-1241427_v")
      (description "Nut")
      (fields
        (field (name "PART NUMBER") "BOSSARD_BN628-1241427_v")
        (field (name "MANUFACTURER") "BOSSARD")
        (field (name "AUTHOR") "CERN DEM JMW")
      )
      (libsource (lib "Eletro-mechanical") (part "Nut"))
    )
    (comp (ref "NUT8")
      (value "M2.5")
      (footprint "BOSSARD_BN628-1241427_v")
      (description "Nut")
      (fields
        (field (name "PART NUMBER") "BOSSARD_BN628-1241427_v")
        (field (name "MANUFACTURER") "BOSSARD")
        (field (name "AUTHOR") "CERN DEM JMW")
      )
      (libsource (lib "Eletro-mechanical") (part "Nut"))
    )
    (comp (ref "NUT9")
      (value "M2.5")
      (footprint "BOSSARD_BN628-1241427_v")
      (description "Nut")
      (fields
        (field (name "PART NUMBER") "BOSSARD_BN628-1241427_v")
        (field (name "MANUFACTURER") "BOSSARD")
        (field (name "AUTHOR") "CERN DEM JMW")
      )
      (libsource (lib "Eletro-mechanical") (part "Nut"))
    )
    (comp (ref "NUT10")
      (value "M2.5")
      (footprint "BOSSARD_BN628-1241427_v")
      (description "Nut")
      (fields
        (field (name "PART NUMBER") "BOSSARD_BN628-1241427_v")
        (field (name "MANUFACTURER") "BOSSARD")
        (field (name "AUTHOR") "CERN DEM JMW")
      )
      (libsource (lib "Eletro-mechanical") (part "Nut"))
    )
    (comp (ref "NUT11")
      (value "M2.5")
      (footprint "BOSSARD_BN628-1241427_v")
      (description "Nut")
      (fields
        (field (name "PART NUMBER") "BOSSARD_BN628-1241427_v")
        (field (name "MANUFACTURER") "BOSSARD")
        (field (name "AUTHOR") "CERN DEM JMW")
      )
      (libsource (lib "Eletro-mechanical") (part "Nut"))
    )
    (comp (ref "SCREW1")
      (value "M2.5x4")
      (footprint "BOSSARD_BN5687-3061587_v")
      (description "Screw")
      (fields
        (field (name "PART NUMBER") "BOSSARD_BN5687-3061587_v")
        (field (name "MANUFACTURER") "BOSSARD")
        (field (name "AUTHOR") "CERN DEM JLC")
      )
      (libsource (lib "Eletro-mechanical") (part "Screw"))
    )
    (comp (ref "SCREW2")
      (value "M2.5x4")
      (footprint "BOSSARD_BN5687-3061587_v")
      (description "Screw")
      (fields
        (field (name "PART NUMBER") "BOSSARD_BN5687-3061587_v")
        (field (name "MANUFACTURER") "BOSSARD")
        (field (name "AUTHOR") "CERN DEM JLC")
      )
      (libsource (lib "Eletro-mechanical") (part "Screw"))
    )
    (comp (ref "SCREW3")
      (value "M2.5x10")
      (footprint "BOSSARD_B2.5X10/BN3333_v")
      (description "Screw; 2.5x10; Head: countersunk; Philips; A1 steel")
      (fields
        (field (name "PART NUMBER") "BOSSARD_B2.5X10/BN3333")
        (field (name "MANUFACTURER") "BOSSARD")
        (field (name "AUTHOR") "GK")
      )
      (libsource (lib "Mechanical") (part "Screw_M2.5x10_Countersunk_v"))
    )
    (comp (ref "SCREW4")
      (value "M2.5x10")
      (footprint "BOSSARD_B2.5X10/BN3333_v")
      (description "Screw; 2.5x10; Head: countersunk; Philips; A1 steel")
      (fields
        (field (name "PART NUMBER") "BOSSARD_B2.5X10/BN3333")
        (field (name "MANUFACTURER") "BOSSARD")
        (field (name "AUTHOR") "GK")
      )
      (libsource (lib "Mechanical") (part "Screw_M2.5x10_Countersunk_v"))
    )
    (comp (ref "SCREW5")
      (value "M2.5x10")
      (footprint "BOSSARD_B2.5X10/BN3333_v")
      (description "Screw; 2.5x10; Head: countersunk; Philips; A1 steel")
      (fields
        (field (name "PART NUMBER") "BOSSARD_B2.5X10/BN3333")
        (field (name "MANUFACTURER") "BOSSARD")
        (field (name "AUTHOR") "GK")
      )
      (libsource (lib "Mechanical") (part "Screw_M2.5x10_Countersunk_v"))
    )
    (comp (ref "SCREW6")
      (value "M2.5x10")
      (footprint "BOSSARD_B2.5X10/BN3333_v")
      (description "Screw; 2.5x10; Head: countersunk; Philips; A1 steel")
      (fields
        (field (name "PART NUMBER") "BOSSARD_B2.5X10/BN3333")
        (field (name "MANUFACTURER") "BOSSARD")
        (field (name "AUTHOR") "GK")
      )
      (libsource (lib "Mechanical") (part "Screw_M2.5x10_Countersunk_v"))
    )
    (comp (ref "SCREW7")
      (value "M2.5x10")
      (footprint "BOSSARD_B2.5X10/BN3333_v")
      (description "Screw; 2.5x10; Head: countersunk; Philips; A1 steel")
      (fields
        (field (name "PART NUMBER") "BOSSARD_B2.5X10/BN3333")
        (field (name "MANUFACTURER") "BOSSARD")
        (field (name "AUTHOR") "GK")
      )
      (libsource (lib "Mechanical") (part "Screw_M2.5x10_Countersunk_v"))
    )
    (comp (ref "SCREW8")
      (value "M2.5x10")
      (footprint "BOSSARD_B2.5X10/BN3333_v")
      (description "Screw; 2.5x10; Head: countersunk; Philips; A1 steel")
      (fields
        (field (name "PART NUMBER") "BOSSARD_B2.5X10/BN3333")
        (field (name "MANUFACTURER") "BOSSARD")
        (field (name "AUTHOR") "GK")
      )
      (libsource (lib "Mechanical") (part "Screw_M2.5x10_Countersunk_v"))
    )
    (comp (ref "SCREW9")
      (value "M2.5x10")
      (footprint "BOSSARD_B2.5X10/BN3333_v")
      (description "Screw; 2.5x10; Head: countersunk; Philips; A1 steel")
      (fields
        (field (name "PART NUMBER") "BOSSARD_B2.5X10/BN3333")
        (field (name "MANUFACTURER") "BOSSARD")
        (field (name "AUTHOR") "GK")
      )
      (libsource (lib "Mechanical") (part "Screw_M2.5x10_Countersunk_v"))
    )
    (comp (ref "SCREW10")
      (value "M2.5x10")
      (footprint "BOSSARD_B2.5X10/BN3333_v")
      (description "Screw; 2.5x10; Head: countersunk; Philips; A1 steel")
      (fields
        (field (name "PART NUMBER") "BOSSARD_B2.5X10/BN3333")
        (field (name "MANUFACTURER") "BOSSARD")
        (field (name "AUTHOR") "GK")
      )
      (libsource (lib "Mechanical") (part "Screw_M2.5x10_Countersunk_v"))
    )
    (comp (ref "SCREW11")
      (value "M2.5x10")
      (footprint "BOSSARD_B2.5X10/BN3333_v")
      (description "Screw; 2.5x10; Head: countersunk; Philips; A1 steel")
      (fields
        (field (name "PART NUMBER") "BOSSARD_B2.5X10/BN3333")
        (field (name "MANUFACTURER") "BOSSARD")
        (field (name "AUTHOR") "GK")
      )
      (libsource (lib "Mechanical") (part "Screw_M2.5x10_Countersunk_v"))
    )
    (comp (ref "ST2")
      (value "SCHROFF_PANEL_3U_8HP_HD68_BNC")
      (footprint "SCHROFF_PANEL_3HP_8U - HD68_BNC")
      (description "Schroff 8HP 3U EUROCARD Panel")
      (fields (field (name "MANUFACTURER") "Schroff") (field (name "MANUFACTURER PART NUMBER") "20849107"))
      (libsource (lib "Mechanical") (part "SCHROFF_PANEL_3U_8HP_HD68_BNC"))
    )
  )
  (nets
    (net (code "1") (name "/DAC_OUT_N1") (class "Default")
      (node (ref "J1") (pin "35") (pinfunction "35_35") (pintype "bidirectional"))
      (node (ref "J2") (pin "2") (pinfunction "2_2") (pintype "bidirectional"))
      (node (ref "J34") (pin "2") (pinfunction "2_2") (pintype "bidirectional"))
      (node (ref "J66") (pin "35") (pinfunction "35_35") (pintype "bidirectional"))
    )
    (net (code "2") (name "/DAC_OUT_N2") (class "Default")
      (node (ref "J1") (pin "36") (pinfunction "36_36") (pintype "bidirectional"))
      (node (ref "J36") (pin "2") (pinfunction "2_2") (pintype "bidirectional"))
      (node (ref "J4") (pin "2") (pinfunction "2_2") (pintype "bidirectional"))
      (node (ref "J66") (pin "36") (pinfunction "36_36") (pintype "bidirectional"))
    )
    (net (code "3") (name "/DAC_OUT_N3") (class "Default")
      (node (ref "J1") (pin "37") (pinfunction "37_37") (pintype "bidirectional"))
      (node (ref "J38") (pin "2") (pinfunction "2_2") (pintype "bidirectional"))
      (node (ref "J6") (pin "2") (pinfunction "2_2") (pintype "bidirectional"))
      (node (ref "J66") (pin "37") (pinfunction "37_37") (pintype "bidirectional"))
    )
    (net (code "4") (name "/DAC_OUT_N4") (class "Default")
      (node (ref "J1") (pin "38") (pinfunction "38_38") (pintype "bidirectional"))
      (node (ref "J40") (pin "2") (pinfunction "2_2") (pintype "bidirectional"))
      (node (ref "J66") (pin "38") (pinfunction "38_38") (pintype "bidirectional"))
      (node (ref "J8") (pin "2") (pinfunction "2_2") (pintype "bidirectional"))
    )
    (net (code "5") (name "/DAC_OUT_N5") (class "Default")
      (node (ref "J1") (pin "39") (pinfunction "39_39") (pintype "bidirectional"))
      (node (ref "J10") (pin "2") (pinfunction "2_2") (pintype "bidirectional"))
      (node (ref "J42") (pin "2") (pinfunction "2_2") (pintype "bidirectional"))
      (node (ref "J66") (pin "39") (pinfunction "39_39") (pintype "bidirectional"))
    )
    (net (code "6") (name "/DAC_OUT_N6") (class "Default")
      (node (ref "J1") (pin "40") (pinfunction "40_40") (pintype "bidirectional"))
      (node (ref "J12") (pin "2") (pinfunction "2_2") (pintype "bidirectional"))
      (node (ref "J44") (pin "2") (pinfunction "2_2") (pintype "bidirectional"))
      (node (ref "J66") (pin "40") (pinfunction "40_40") (pintype "bidirectional"))
    )
    (net (code "7") (name "/DAC_OUT_N7") (class "Default")
      (node (ref "J1") (pin "41") (pinfunction "41_41") (pintype "bidirectional"))
      (node (ref "J14") (pin "2") (pinfunction "2_2") (pintype "bidirectional"))
      (node (ref "J46") (pin "2") (pinfunction "2_2") (pintype "bidirectional"))
      (node (ref "J66") (pin "41") (pinfunction "41_41") (pintype "bidirectional"))
    )
    (net (code "8") (name "/DAC_OUT_N8") (class "Default")
      (node (ref "J1") (pin "42") (pinfunction "42_42") (pintype "bidirectional"))
      (node (ref "J16") (pin "2") (pinfunction "2_2") (pintype "bidirectional"))
      (node (ref "J48") (pin "2") (pinfunction "2_2") (pintype "bidirectional"))
      (node (ref "J66") (pin "42") (pinfunction "42_42") (pintype "bidirectional"))
    )
    (net (code "9") (name "/DAC_OUT_N9") (class "Default")
      (node (ref "J1") (pin "43") (pinfunction "43_43") (pintype "bidirectional"))
      (node (ref "J3") (pin "2") (pinfunction "2_2") (pintype "bidirectional"))
      (node (ref "J35") (pin "2") (pinfunction "2_2") (pintype "bidirectional"))
      (node (ref "J66") (pin "43") (pinfunction "43_43") (pintype "bidirectional"))
    )
    (net (code "10") (name "/DAC_OUT_N10") (class "Default")
      (node (ref "J1") (pin "44") (pinfunction "44_44") (pintype "bidirectional"))
      (node (ref "J37") (pin "2") (pinfunction "2_2") (pintype "bidirectional"))
      (node (ref "J5") (pin "2") (pinfunction "2_2") (pintype "bidirectional"))
      (node (ref "J66") (pin "44") (pinfunction "44_44") (pintype "bidirectional"))
    )
    (net (code "11") (name "/DAC_OUT_N11") (class "Default")
      (node (ref "J1") (pin "45") (pinfunction "45_45") (pintype "bidirectional"))
      (node (ref "J39") (pin "2") (pinfunction "2_2") (pintype "bidirectional"))
      (node (ref "J66") (pin "45") (pinfunction "45_45") (pintype "bidirectional"))
      (node (ref "J7") (pin "2") (pinfunction "2_2") (pintype "bidirectional"))
    )
    (net (code "12") (name "/DAC_OUT_N12") (class "Default")
      (node (ref "J1") (pin "46") (pinfunction "46_46") (pintype "bidirectional"))
      (node (ref "J41") (pin "2") (pinfunction "2_2") (pintype "bidirectional"))
      (node (ref "J66") (pin "46") (pinfunction "46_46") (pintype "bidirectional"))
      (node (ref "J9") (pin "2") (pinfunction "2_2") (pintype "bidirectional"))
    )
    (net (code "13") (name "/DAC_OUT_N13") (class "Default")
      (node (ref "J1") (pin "47") (pinfunction "47_47") (pintype "bidirectional"))
      (node (ref "J11") (pin "2") (pinfunction "2_2") (pintype "bidirectional"))
      (node (ref "J43") (pin "2") (pinfunction "2_2") (pintype "bidirectional"))
      (node (ref "J66") (pin "47") (pinfunction "47_47") (pintype "bidirectional"))
    )
    (net (code "14") (name "/DAC_OUT_N14") (class "Default")
      (node (ref "J1") (pin "48") (pinfunction "48_48") (pintype "bidirectional"))
      (node (ref "J13") (pin "2") (pinfunction "2_2") (pintype "bidirectional"))
      (node (ref "J45") (pin "2") (pinfunction "2_2") (pintype "bidirectional"))
      (node (ref "J66") (pin "48") (pinfunction "48_48") (pintype "bidirectional"))
    )
    (net (code "15") (name "/DAC_OUT_N15") (class "Default")
      (node (ref "J1") (pin "49") (pinfunction "49_49") (pintype "bidirectional"))
      (node (ref "J15") (pin "2") (pinfunction "2_2") (pintype "bidirectional"))
      (node (ref "J47") (pin "2") (pinfunction "2_2") (pintype "bidirectional"))
      (node (ref "J66") (pin "49") (pinfunction "49_49") (pintype "bidirectional"))
    )
    (net (code "16") (name "/DAC_OUT_N16") (class "Default")
      (node (ref "J1") (pin "50") (pinfunction "50_50") (pintype "bidirectional"))
      (node (ref "J17") (pin "2") (pinfunction "2_2") (pintype "bidirectional"))
      (node (ref "J49") (pin "2") (pinfunction "2_2") (pintype "bidirectional"))
      (node (ref "J66") (pin "50") (pinfunction "50_50") (pintype "bidirectional"))
    )
    (net (code "17") (name "/DAC_OUT_N17") (class "Default")
      (node (ref "J1") (pin "53") (pinfunction "53_53") (pintype "bidirectional"))
      (node (ref "J18") (pin "2") (pinfunction "2_2") (pintype "bidirectional"))
      (node (ref "J50") (pin "2") (pinfunction "2_2") (pintype "bidirectional"))
      (node (ref "J66") (pin "53") (pinfunction "53_53") (pintype "bidirectional"))
    )
    (net (code "18") (name "/DAC_OUT_N18") (class "Default")
      (node (ref "J1") (pin "54") (pinfunction "54_54") (pintype "bidirectional"))
      (node (ref "J20") (pin "2") (pinfunction "2_2") (pintype "bidirectional"))
      (node (ref "J52") (pin "2") (pinfunction "2_2") (pintype "bidirectional"))
      (node (ref "J66") (pin "54") (pinfunction "54_54") (pintype "bidirectional"))
    )
    (net (code "19") (name "/DAC_OUT_N19") (class "Default")
      (node (ref "J1") (pin "55") (pinfunction "55_55") (pintype "bidirectional"))
      (node (ref "J22") (pin "2") (pinfunction "2_2") (pintype "bidirectional"))
      (node (ref "J54") (pin "2") (pinfunction "2_2") (pintype "bidirectional"))
      (node (ref "J66") (pin "55") (pinfunction "55_55") (pintype "bidirectional"))
    )
    (net (code "20") (name "/DAC_OUT_N20") (class "Default")
      (node (ref "J1") (pin "56") (pinfunction "56_56") (pintype "bidirectional"))
      (node (ref "J24") (pin "2") (pinfunction "2_2") (pintype "bidirectional"))
      (node (ref "J56") (pin "2") (pinfunction "2_2") (pintype "bidirectional"))
      (node (ref "J66") (pin "56") (pinfunction "56_56") (pintype "bidirectional"))
    )
    (net (code "21") (name "/DAC_OUT_N21") (class "Default")
      (node (ref "J1") (pin "57") (pinfunction "57_57") (pintype "bidirectional"))
      (node (ref "J26") (pin "2") (pinfunction "2_2") (pintype "bidirectional"))
      (node (ref "J58") (pin "2") (pinfunction "2_2") (pintype "bidirectional"))
      (node (ref "J66") (pin "57") (pinfunction "57_57") (pintype "bidirectional"))
    )
    (net (code "22") (name "/DAC_OUT_N22") (class "Default")
      (node (ref "J1") (pin "58") (pinfunction "58_58") (pintype "bidirectional"))
      (node (ref "J28") (pin "2") (pinfunction "2_2") (pintype "bidirectional"))
      (node (ref "J60") (pin "2") (pinfunction "2_2") (pintype "bidirectional"))
      (node (ref "J66") (pin "58") (pinfunction "58_58") (pintype "bidirectional"))
    )
    (net (code "23") (name "/DAC_OUT_N23") (class "Default")
      (node (ref "J1") (pin "59") (pinfunction "59_59") (pintype "bidirectional"))
      (node (ref "J30") (pin "2") (pinfunction "2_2") (pintype "bidirectional"))
      (node (ref "J62") (pin "2") (pinfunction "2_2") (pintype "bidirectional"))
      (node (ref "J66") (pin "59") (pinfunction "59_59") (pintype "bidirectional"))
    )
    (net (code "24") (name "/DAC_OUT_N24") (class "Default")
      (node (ref "J1") (pin "60") (pinfunction "60_60") (pintype "bidirectional"))
      (node (ref "J32") (pin "2") (pinfunction "2_2") (pintype "bidirectional"))
      (node (ref "J64") (pin "2") (pinfunction "2_2") (pintype "bidirectional"))
      (node (ref "J66") (pin "60") (pinfunction "60_60") (pintype "bidirectional"))
    )
    (net (code "25") (name "/DAC_OUT_N25") (class "Default")
      (node (ref "J1") (pin "61") (pinfunction "61_61") (pintype "bidirectional"))
      (node (ref "J19") (pin "2") (pinfunction "2_2") (pintype "bidirectional"))
      (node (ref "J51") (pin "2") (pinfunction "2_2") (pintype "bidirectional"))
      (node (ref "J66") (pin "61") (pinfunction "61_61") (pintype "bidirectional"))
    )
    (net (code "26") (name "/DAC_OUT_N26") (class "Default")
      (node (ref "J1") (pin "62") (pinfunction "62_62") (pintype "bidirectional"))
      (node (ref "J21") (pin "2") (pinfunction "2_2") (pintype "bidirectional"))
      (node (ref "J53") (pin "2") (pinfunction "2_2") (pintype "bidirectional"))
      (node (ref "J66") (pin "62") (pinfunction "62_62") (pintype "bidirectional"))
    )
    (net (code "27") (name "/DAC_OUT_N27") (class "Default")
      (node (ref "J1") (pin "63") (pinfunction "63_63") (pintype "bidirectional"))
      (node (ref "J23") (pin "2") (pinfunction "2_2") (pintype "bidirectional"))
      (node (ref "J55") (pin "2") (pinfunction "2_2") (pintype "bidirectional"))
      (node (ref "J66") (pin "63") (pinfunction "63_63") (pintype "bidirectional"))
    )
    (net (code "28") (name "/DAC_OUT_N28") (class "Default")
      (node (ref "J1") (pin "64") (pinfunction "64_64") (pintype "bidirectional"))
      (node (ref "J25") (pin "2") (pinfunction "2_2") (pintype "bidirectional"))
      (node (ref "J57") (pin "2") (pinfunction "2_2") (pintype "bidirectional"))
      (node (ref "J66") (pin "64") (pinfunction "64_64") (pintype "bidirectional"))
    )
    (net (code "29") (name "/DAC_OUT_N29") (class "Default")
      (node (ref "J1") (pin "65") (pinfunction "65_65") (pintype "bidirectional"))
      (node (ref "J27") (pin "2") (pinfunction "2_2") (pintype "bidirectional"))
      (node (ref "J59") (pin "2") (pinfunction "2_2") (pintype "bidirectional"))
      (node (ref "J66") (pin "65") (pinfunction "65_65") (pintype "bidirectional"))
    )
    (net (code "30") (name "/DAC_OUT_N30") (class "Default")
      (node (ref "J1") (pin "66") (pinfunction "66_66") (pintype "bidirectional"))
      (node (ref "J29") (pin "2") (pinfunction "2_2") (pintype "bidirectional"))
      (node (ref "J61") (pin "2") (pinfunction "2_2") (pintype "bidirectional"))
      (node (ref "J66") (pin "66") (pinfunction "66_66") (pintype "bidirectional"))
    )
    (net (code "31") (name "/DAC_OUT_N31") (class "Default")
      (node (ref "J1") (pin "67") (pinfunction "67_67") (pintype "bidirectional"))
      (node (ref "J31") (pin "2") (pinfunction "2_2") (pintype "bidirectional"))
      (node (ref "J63") (pin "2") (pinfunction "2_2") (pintype "bidirectional"))
      (node (ref "J66") (pin "67") (pinfunction "67_67") (pintype "bidirectional"))
    )
    (net (code "32") (name "/DAC_OUT_N32") (class "Default")
      (node (ref "J1") (pin "68") (pinfunction "68_68") (pintype "bidirectional"))
      (node (ref "J33") (pin "2") (pinfunction "2_2") (pintype "bidirectional"))
      (node (ref "J65") (pin "2") (pinfunction "2_2") (pintype "bidirectional"))
      (node (ref "J66") (pin "68") (pinfunction "68_68") (pintype "bidirectional"))
    )
    (net (code "33") (name "/DAC_OUT_P1") (class "Default")
      (node (ref "J1") (pin "1") (pinfunction "1_1") (pintype "bidirectional"))
      (node (ref "J2") (pin "1") (pinfunction "1_1") (pintype "bidirectional"))
      (node (ref "J34") (pin "1") (pinfunction "1_1") (pintype "bidirectional"))
      (node (ref "J66") (pin "1") (pinfunction "1_1") (pintype "bidirectional"))
    )
    (net (code "34") (name "/DAC_OUT_P2") (class "Default")
      (node (ref "J1") (pin "2") (pinfunction "2_2") (pintype "bidirectional"))
      (node (ref "J36") (pin "1") (pinfunction "1_1") (pintype "bidirectional"))
      (node (ref "J4") (pin "1") (pinfunction "1_1") (pintype "bidirectional"))
      (node (ref "J66") (pin "2") (pinfunction "2_2") (pintype "bidirectional"))
    )
    (net (code "35") (name "/DAC_OUT_P3") (class "Default")
      (node (ref "J1") (pin "3") (pinfunction "3_3") (pintype "bidirectional"))
      (node (ref "J38") (pin "1") (pinfunction "1_1") (pintype "bidirectional"))
      (node (ref "J6") (pin "1") (pinfunction "1_1") (pintype "bidirectional"))
      (node (ref "J66") (pin "3") (pinfunction "3_3") (pintype "bidirectional"))
    )
    (net (code "36") (name "/DAC_OUT_P4") (class "Default")
      (node (ref "J1") (pin "4") (pinfunction "4_4") (pintype "bidirectional"))
      (node (ref "J40") (pin "1") (pinfunction "1_1") (pintype "bidirectional"))
      (node (ref "J66") (pin "4") (pinfunction "4_4") (pintype "bidirectional"))
      (node (ref "J8") (pin "1") (pinfunction "1_1") (pintype "bidirectional"))
    )
    (net (code "37") (name "/DAC_OUT_P5") (class "Default")
      (node (ref "J1") (pin "5") (pinfunction "5_5") (pintype "bidirectional"))
      (node (ref "J10") (pin "1") (pinfunction "1_1") (pintype "bidirectional"))
      (node (ref "J42") (pin "1") (pinfunction "1_1") (pintype "bidirectional"))
      (node (ref "J66") (pin "5") (pinfunction "5_5") (pintype "bidirectional"))
    )
    (net (code "38") (name "/DAC_OUT_P6") (class "Default")
      (node (ref "J1") (pin "6") (pinfunction "6_6") (pintype "bidirectional"))
      (node (ref "J12") (pin "1") (pinfunction "1_1") (pintype "bidirectional"))
      (node (ref "J44") (pin "1") (pinfunction "1_1") (pintype "bidirectional"))
      (node (ref "J66") (pin "6") (pinfunction "6_6") (pintype "bidirectional"))
    )
    (net (code "39") (name "/DAC_OUT_P7") (class "Default")
      (node (ref "J1") (pin "7") (pinfunction "7_7") (pintype "bidirectional"))
      (node (ref "J14") (pin "1") (pinfunction "1_1") (pintype "bidirectional"))
      (node (ref "J46") (pin "1") (pinfunction "1_1") (pintype "bidirectional"))
      (node (ref "J66") (pin "7") (pinfunction "7_7") (pintype "bidirectional"))
    )
    (net (code "40") (name "/DAC_OUT_P8") (class "Default")
      (node (ref "J1") (pin "8") (pinfunction "8_8") (pintype "bidirectional"))
      (node (ref "J16") (pin "1") (pinfunction "1_1") (pintype "bidirectional"))
      (node (ref "J48") (pin "1") (pinfunction "1_1") (pintype "bidirectional"))
      (node (ref "J66") (pin "8") (pinfunction "8_8") (pintype "bidirectional"))
    )
    (net (code "41") (name "/DAC_OUT_P9") (class "Default")
      (node (ref "J1") (pin "9") (pinfunction "9_9") (pintype "bidirectional"))
      (node (ref "J3") (pin "1") (pinfunction "1_1") (pintype "bidirectional"))
      (node (ref "J35") (pin "1") (pinfunction "1_1") (pintype "bidirectional"))
      (node (ref "J66") (pin "9") (pinfunction "9_9") (pintype "bidirectional"))
    )
    (net (code "42") (name "/DAC_OUT_P10") (class "Default")
      (node (ref "J1") (pin "10") (pinfunction "10_10") (pintype "bidirectional"))
      (node (ref "J37") (pin "1") (pinfunction "1_1") (pintype "bidirectional"))
      (node (ref "J5") (pin "1") (pinfunction "1_1") (pintype "bidirectional"))
      (node (ref "J66") (pin "10") (pinfunction "10_10") (pintype "bidirectional"))
    )
    (net (code "43") (name "/DAC_OUT_P11") (class "Default")
      (node (ref "J1") (pin "11") (pinfunction "11_11") (pintype "bidirectional"))
      (node (ref "J39") (pin "1") (pinfunction "1_1") (pintype "bidirectional"))
      (node (ref "J66") (pin "11") (pinfunction "11_11") (pintype "bidirectional"))
      (node (ref "J7") (pin "1") (pinfunction "1_1") (pintype "bidirectional"))
    )
    (net (code "44") (name "/DAC_OUT_P12") (class "Default")
      (node (ref "J1") (pin "12") (pinfunction "12_12") (pintype "bidirectional"))
      (node (ref "J41") (pin "1") (pinfunction "1_1") (pintype "bidirectional"))
      (node (ref "J66") (pin "12") (pinfunction "12_12") (pintype "bidirectional"))
      (node (ref "J9") (pin "1") (pinfunction "1_1") (pintype "bidirectional"))
    )
    (net (code "45") (name "/DAC_OUT_P13") (class "Default")
      (node (ref "J1") (pin "13") (pinfunction "13_13") (pintype "bidirectional"))
      (node (ref "J11") (pin "1") (pinfunction "1_1") (pintype "bidirectional"))
      (node (ref "J43") (pin "1") (pinfunction "1_1") (pintype "bidirectional"))
      (node (ref "J66") (pin "13") (pinfunction "13_13") (pintype "bidirectional"))
    )
    (net (code "46") (name "/DAC_OUT_P14") (class "Default")
      (node (ref "J1") (pin "14") (pinfunction "14_14") (pintype "bidirectional"))
      (node (ref "J13") (pin "1") (pinfunction "1_1") (pintype "bidirectional"))
      (node (ref "J45") (pin "1") (pinfunction "1_1") (pintype "bidirectional"))
      (node (ref "J66") (pin "14") (pinfunction "14_14") (pintype "bidirectional"))
    )
    (net (code "47") (name "/DAC_OUT_P15") (class "Default")
      (node (ref "J1") (pin "15") (pinfunction "15_15") (pintype "bidirectional"))
      (node (ref "J15") (pin "1") (pinfunction "1_1") (pintype "bidirectional"))
      (node (ref "J47") (pin "1") (pinfunction "1_1") (pintype "bidirectional"))
      (node (ref "J66") (pin "15") (pinfunction "15_15") (pintype "bidirectional"))
    )
    (net (code "48") (name "/DAC_OUT_P16") (class "Default")
      (node (ref "J1") (pin "16") (pinfunction "16_16") (pintype "bidirectional"))
      (node (ref "J17") (pin "1") (pinfunction "1_1") (pintype "bidirectional"))
      (node (ref "J49") (pin "1") (pinfunction "1_1") (pintype "bidirectional"))
      (node (ref "J66") (pin "16") (pinfunction "16_16") (pintype "bidirectional"))
    )
    (net (code "49") (name "/DAC_OUT_P17") (class "Default")
      (node (ref "J1") (pin "19") (pinfunction "19_19") (pintype "bidirectional"))
      (node (ref "J18") (pin "1") (pinfunction "1_1") (pintype "bidirectional"))
      (node (ref "J50") (pin "1") (pinfunction "1_1") (pintype "bidirectional"))
      (node (ref "J66") (pin "19") (pinfunction "19_19") (pintype "bidirectional"))
    )
    (net (code "50") (name "/DAC_OUT_P18") (class "Default")
      (node (ref "J1") (pin "20") (pinfunction "20_20") (pintype "bidirectional"))
      (node (ref "J20") (pin "1") (pinfunction "1_1") (pintype "bidirectional"))
      (node (ref "J52") (pin "1") (pinfunction "1_1") (pintype "bidirectional"))
      (node (ref "J66") (pin "20") (pinfunction "20_20") (pintype "bidirectional"))
    )
    (net (code "51") (name "/DAC_OUT_P19") (class "Default")
      (node (ref "J1") (pin "21") (pinfunction "21_21") (pintype "bidirectional"))
      (node (ref "J22") (pin "1") (pinfunction "1_1") (pintype "bidirectional"))
      (node (ref "J54") (pin "1") (pinfunction "1_1") (pintype "bidirectional"))
      (node (ref "J66") (pin "21") (pinfunction "21_21") (pintype "bidirectional"))
    )
    (net (code "52") (name "/DAC_OUT_P20") (class "Default")
      (node (ref "J1") (pin "22") (pinfunction "22_22") (pintype "bidirectional"))
      (node (ref "J24") (pin "1") (pinfunction "1_1") (pintype "bidirectional"))
      (node (ref "J56") (pin "1") (pinfunction "1_1") (pintype "bidirectional"))
      (node (ref "J66") (pin "22") (pinfunction "22_22") (pintype "bidirectional"))
    )
    (net (code "53") (name "/DAC_OUT_P21") (class "Default")
      (node (ref "J1") (pin "23") (pinfunction "23_23") (pintype "bidirectional"))
      (node (ref "J26") (pin "1") (pinfunction "1_1") (pintype "bidirectional"))
      (node (ref "J58") (pin "1") (pinfunction "1_1") (pintype "bidirectional"))
      (node (ref "J66") (pin "23") (pinfunction "23_23") (pintype "bidirectional"))
    )
    (net (code "54") (name "/DAC_OUT_P22") (class "Default")
      (node (ref "J1") (pin "24") (pinfunction "24_24") (pintype "bidirectional"))
      (node (ref "J28") (pin "1") (pinfunction "1_1") (pintype "bidirectional"))
      (node (ref "J60") (pin "1") (pinfunction "1_1") (pintype "bidirectional"))
      (node (ref "J66") (pin "24") (pinfunction "24_24") (pintype "bidirectional"))
    )
    (net (code "55") (name "/DAC_OUT_P23") (class "Default")
      (node (ref "J1") (pin "25") (pinfunction "25_25") (pintype "bidirectional"))
      (node (ref "J30") (pin "1") (pinfunction "1_1") (pintype "bidirectional"))
      (node (ref "J62") (pin "1") (pinfunction "1_1") (pintype "bidirectional"))
      (node (ref "J66") (pin "25") (pinfunction "25_25") (pintype "bidirectional"))
    )
    (net (code "56") (name "/DAC_OUT_P24") (class "Default")
      (node (ref "J1") (pin "26") (pinfunction "26_26") (pintype "bidirectional"))
      (node (ref "J32") (pin "1") (pinfunction "1_1") (pintype "bidirectional"))
      (node (ref "J64") (pin "1") (pinfunction "1_1") (pintype "bidirectional"))
      (node (ref "J66") (pin "26") (pinfunction "26_26") (pintype "bidirectional"))
    )
    (net (code "57") (name "/DAC_OUT_P25") (class "Default")
      (node (ref "J1") (pin "27") (pinfunction "27_27") (pintype "bidirectional"))
      (node (ref "J19") (pin "1") (pinfunction "1_1") (pintype "bidirectional"))
      (node (ref "J51") (pin "1") (pinfunction "1_1") (pintype "bidirectional"))
      (node (ref "J66") (pin "27") (pinfunction "27_27") (pintype "bidirectional"))
    )
    (net (code "58") (name "/DAC_OUT_P26") (class "Default")
      (node (ref "J1") (pin "28") (pinfunction "28_28") (pintype "bidirectional"))
      (node (ref "J21") (pin "1") (pinfunction "1_1") (pintype "bidirectional"))
      (node (ref "J53") (pin "1") (pinfunction "1_1") (pintype "bidirectional"))
      (node (ref "J66") (pin "28") (pinfunction "28_28") (pintype "bidirectional"))
    )
    (net (code "59") (name "/DAC_OUT_P27") (class "Default")
      (node (ref "J1") (pin "29") (pinfunction "29_29") (pintype "bidirectional"))
      (node (ref "J23") (pin "1") (pinfunction "1_1") (pintype "bidirectional"))
      (node (ref "J55") (pin "1") (pinfunction "1_1") (pintype "bidirectional"))
      (node (ref "J66") (pin "29") (pinfunction "29_29") (pintype "bidirectional"))
    )
    (net (code "60") (name "/DAC_OUT_P28") (class "Default")
      (node (ref "J1") (pin "30") (pinfunction "30_30") (pintype "bidirectional"))
      (node (ref "J25") (pin "1") (pinfunction "1_1") (pintype "bidirectional"))
      (node (ref "J57") (pin "1") (pinfunction "1_1") (pintype "bidirectional"))
      (node (ref "J66") (pin "30") (pinfunction "30_30") (pintype "bidirectional"))
    )
    (net (code "61") (name "/DAC_OUT_P29") (class "Default")
      (node (ref "J1") (pin "31") (pinfunction "31_31") (pintype "bidirectional"))
      (node (ref "J27") (pin "1") (pinfunction "1_1") (pintype "bidirectional"))
      (node (ref "J59") (pin "1") (pinfunction "1_1") (pintype "bidirectional"))
      (node (ref "J66") (pin "31") (pinfunction "31_31") (pintype "bidirectional"))
    )
    (net (code "62") (name "/DAC_OUT_P30") (class "Default")
      (node (ref "J1") (pin "32") (pinfunction "32_32") (pintype "bidirectional"))
      (node (ref "J29") (pin "1") (pinfunction "1_1") (pintype "bidirectional"))
      (node (ref "J61") (pin "1") (pinfunction "1_1") (pintype "bidirectional"))
      (node (ref "J66") (pin "32") (pinfunction "32_32") (pintype "bidirectional"))
    )
    (net (code "63") (name "/DAC_OUT_P31") (class "Default")
      (node (ref "J1") (pin "33") (pinfunction "33_33") (pintype "bidirectional"))
      (node (ref "J31") (pin "1") (pinfunction "1_1") (pintype "bidirectional"))
      (node (ref "J63") (pin "1") (pinfunction "1_1") (pintype "bidirectional"))
      (node (ref "J66") (pin "33") (pinfunction "33_33") (pintype "bidirectional"))
    )
    (net (code "64") (name "/DAC_OUT_P32") (class "Default")
      (node (ref "J1") (pin "34") (pinfunction "34_34") (pintype "bidirectional"))
      (node (ref "J33") (pin "1") (pinfunction "1_1") (pintype "bidirectional"))
      (node (ref "J65") (pin "1") (pinfunction "1_1") (pintype "bidirectional"))
      (node (ref "J66") (pin "34") (pinfunction "34_34") (pintype "bidirectional"))
    )
    (net (code "65") (name "GND") (class "Default")
      (node (ref "B1") (pin "1") (pinfunction "1_1") (pintype "bidirectional"))
      (node (ref "B2") (pin "1") (pinfunction "1_1") (pintype "bidirectional"))
      (node (ref "B3") (pin "1") (pinfunction "1_1") (pintype "bidirectional"))
      (node (ref "B4") (pin "1") (pinfunction "1_1") (pintype "bidirectional"))
      (node (ref "B7") (pin "1") (pinfunction "1_1") (pintype "bidirectional"))
      (node (ref "B8") (pin "1") (pinfunction "1_1") (pintype "bidirectional"))
      (node (ref "B9") (pin "1") (pinfunction "1_1") (pintype "bidirectional"))
      (node (ref "J1") (pin "17") (pinfunction "17_17") (pintype "bidirectional"))
      (node (ref "J1") (pin "51") (pinfunction "51_51") (pintype "bidirectional"))
      (node (ref "J1") (pin "69") (pinfunction "69_69") (pintype "bidirectional"))
      (node (ref "J1") (pin "70") (pinfunction "70_70") (pintype "bidirectional"))
      (node (ref "J66") (pin "17") (pinfunction "17_17") (pintype "bidirectional"))
      (node (ref "J66") (pin "51") (pinfunction "51_51") (pintype "bidirectional"))
      (node (ref "J66") (pin "69") (pinfunction "69_69") (pintype "passive"))
      (node (ref "J66") (pin "70") (pinfunction "70_70") (pintype "passive"))
      (node (ref "ST2") (pin "0") (pinfunction "0_0") (pintype "passive"))
      (node (ref "ST2") (pin "1") (pinfunction "1_1") (pintype "passive"))
    )
    (net (code "66") (name "N13V0_SCSI") (class "Default")
      (node (ref "J1") (pin "52") (pinfunction "52_52") (pintype "bidirectional"))
      (node (ref "J66") (pin "52") (pinfunction "52_52") (pintype "bidirectional"))
    )
    (net (code "67") (name "P13V0_SCSI") (class "Default")
      (node (ref "J1") (pin "18") (pinfunction "18_18") (pintype "bidirectional"))
      (node (ref "J66") (pin "18") (pinfunction "18_18") (pintype "bidirectional"))
    )
  )
)
